# mcore-h616-breakout-RevA1.net
KiCad netlist of a schematic drawn in EAGLE
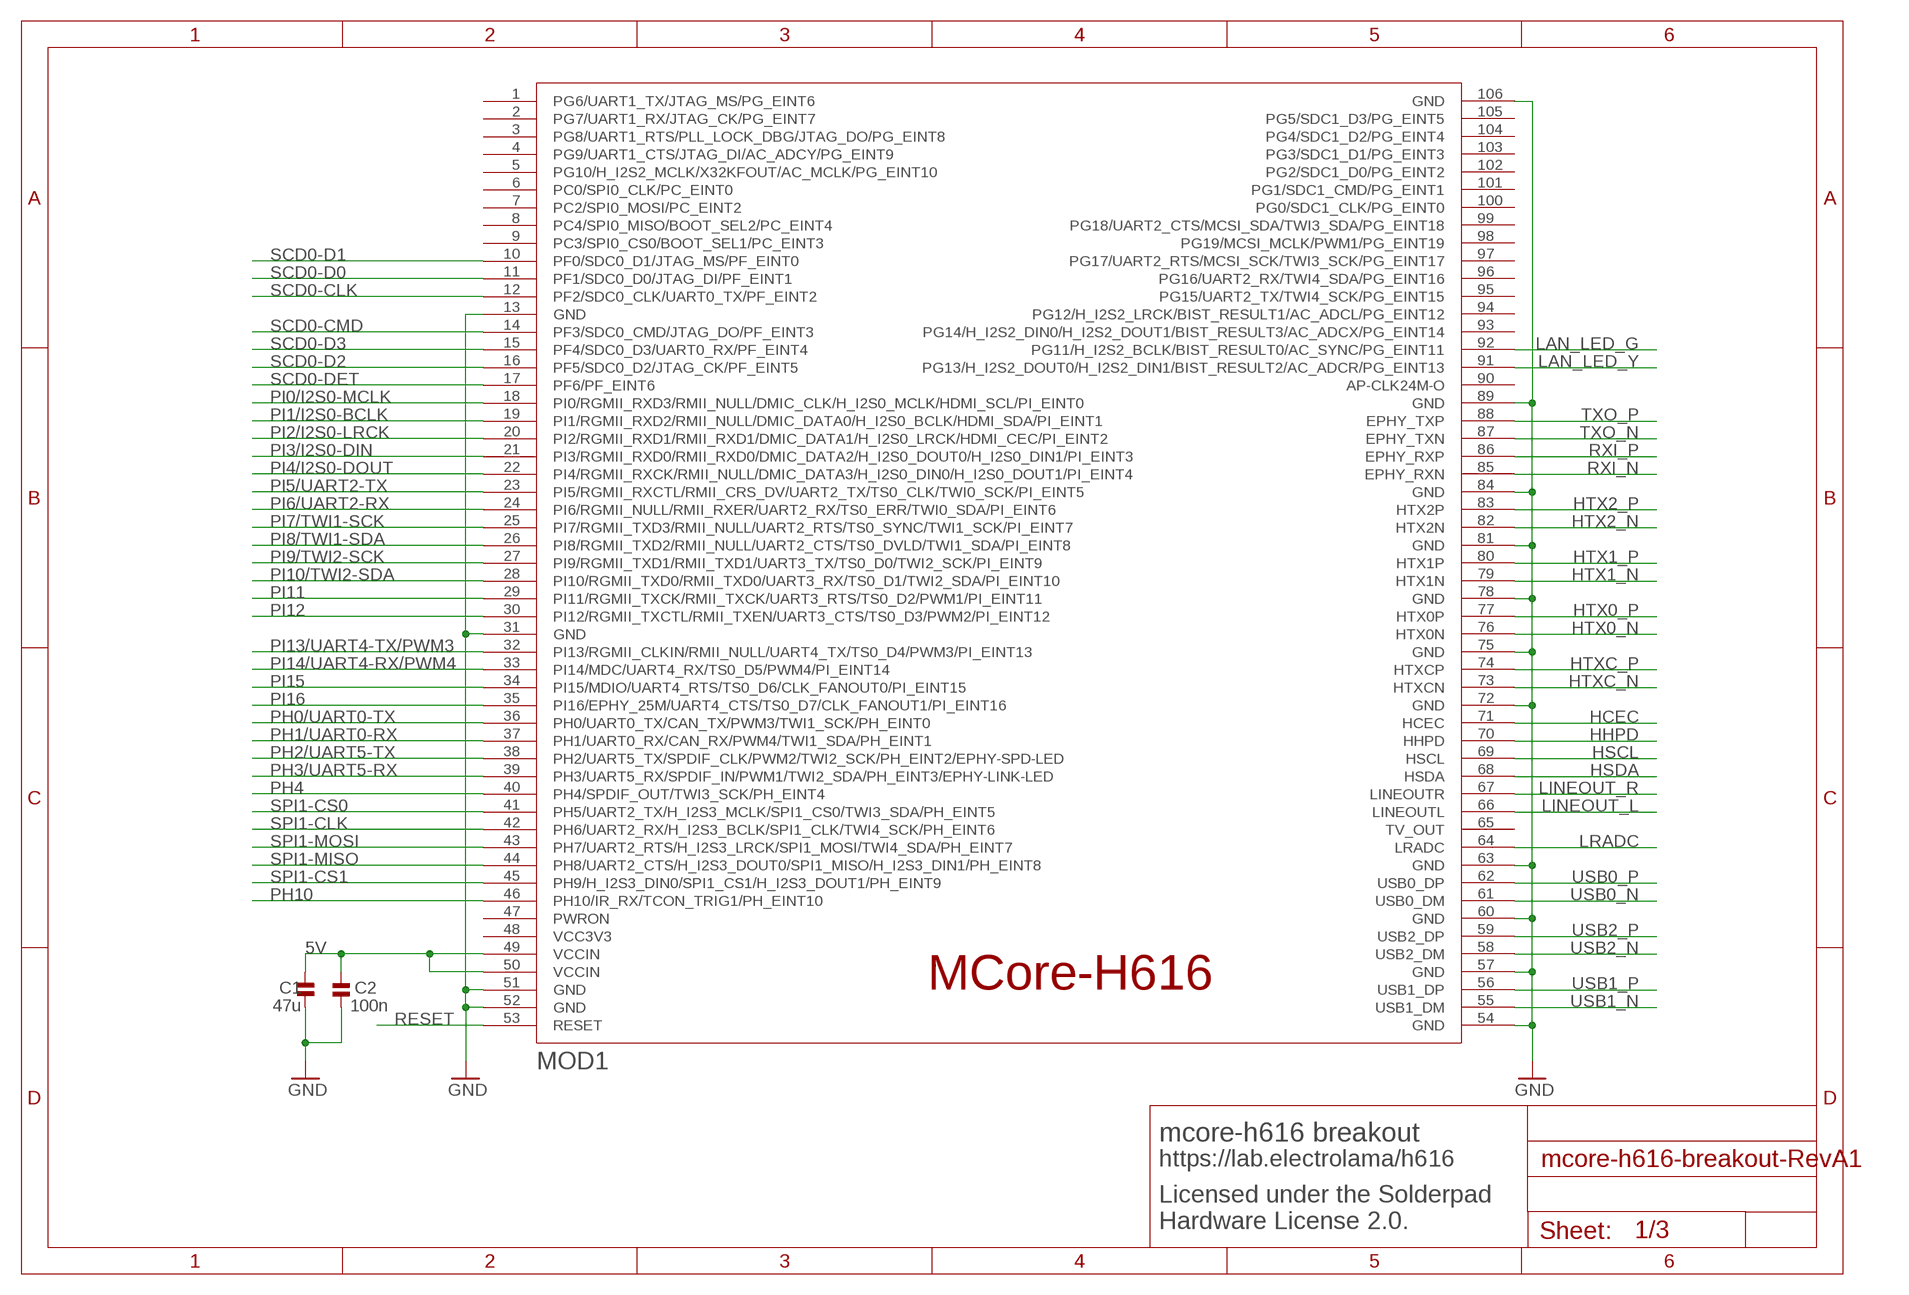
[diagram p0: schematic, sheet 1]
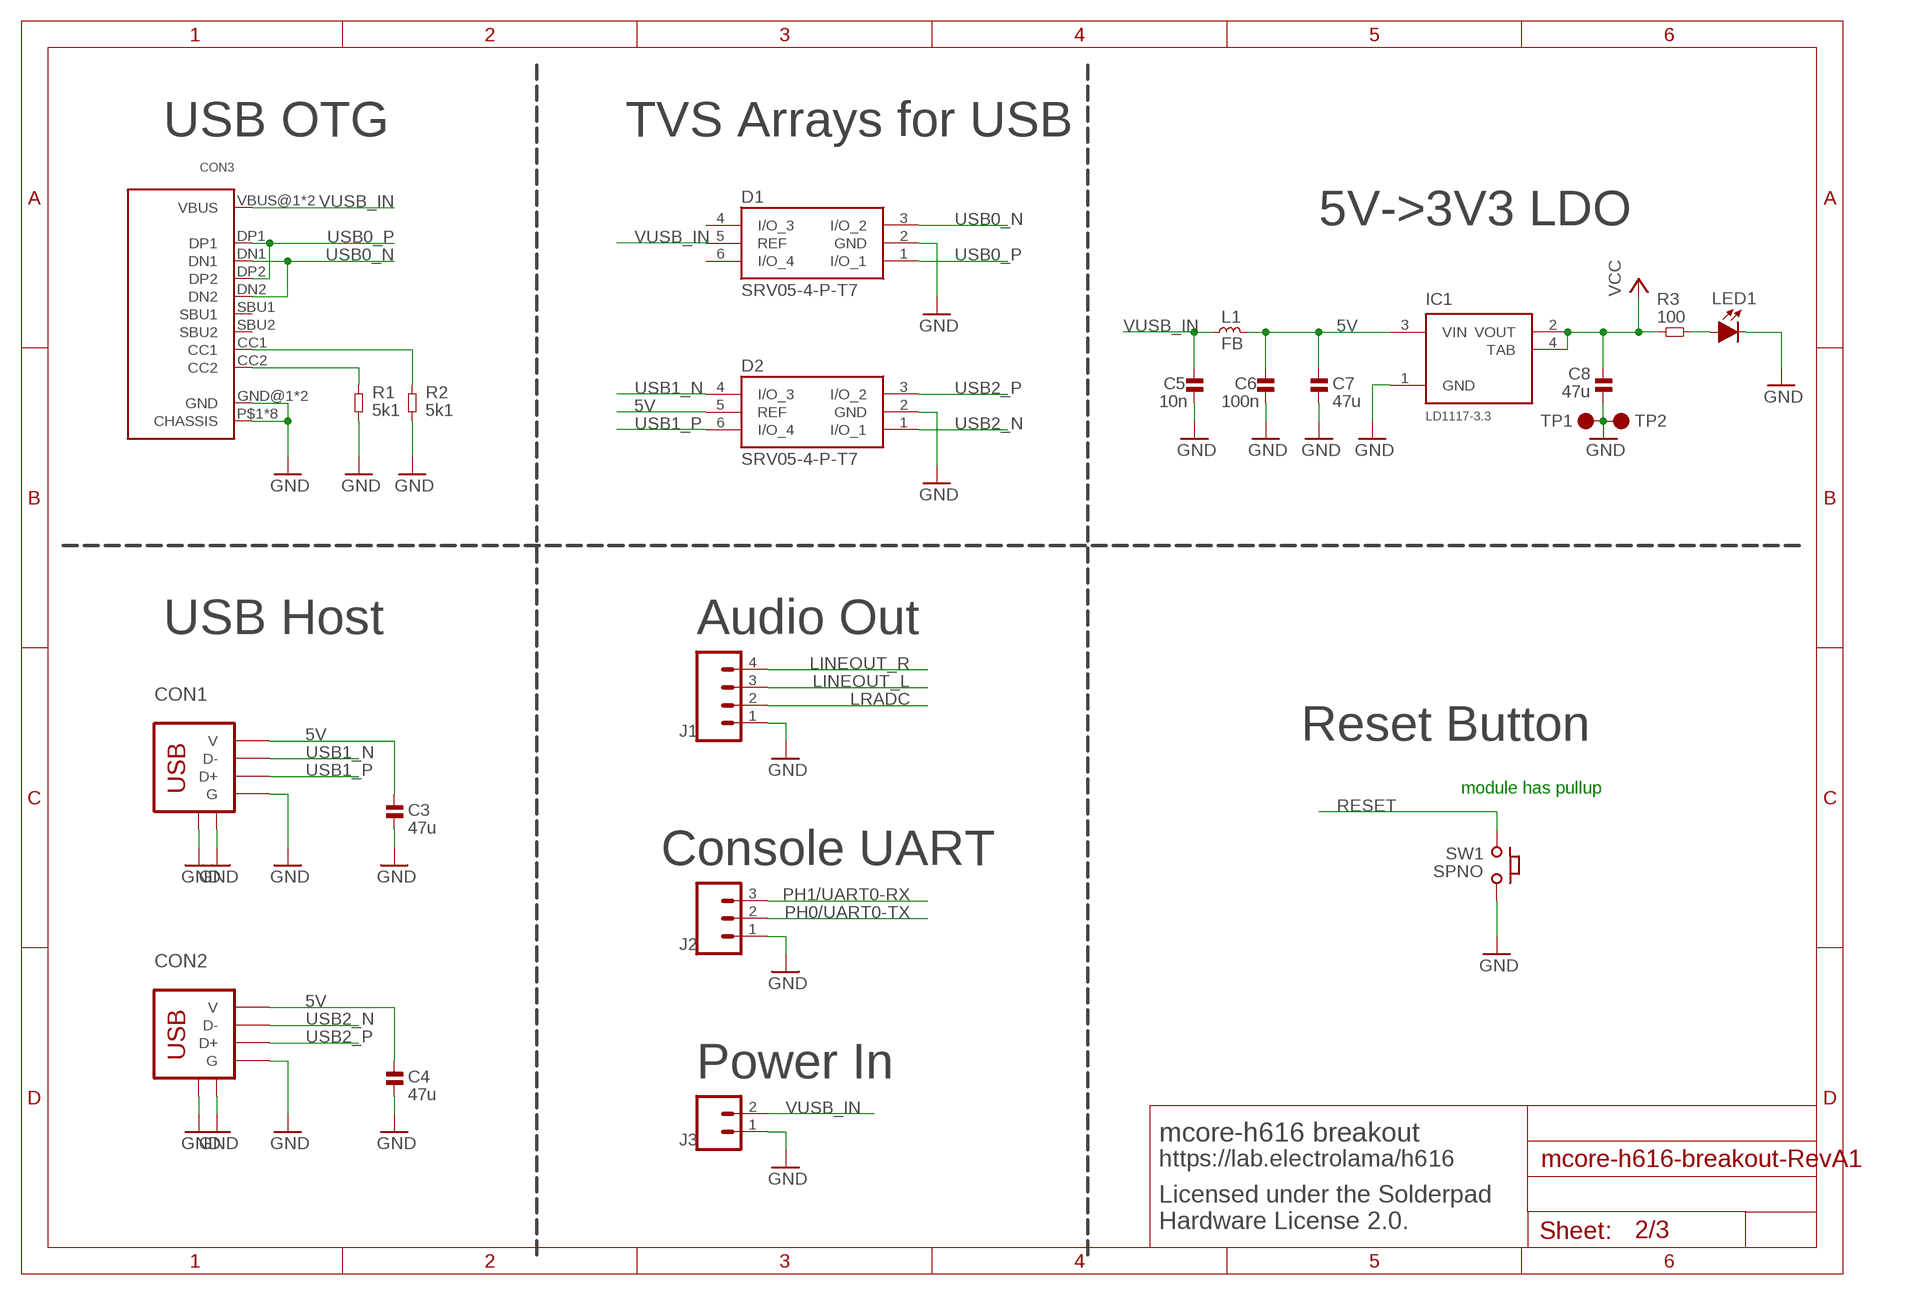
[diagram p1: schematic, sheet 2]
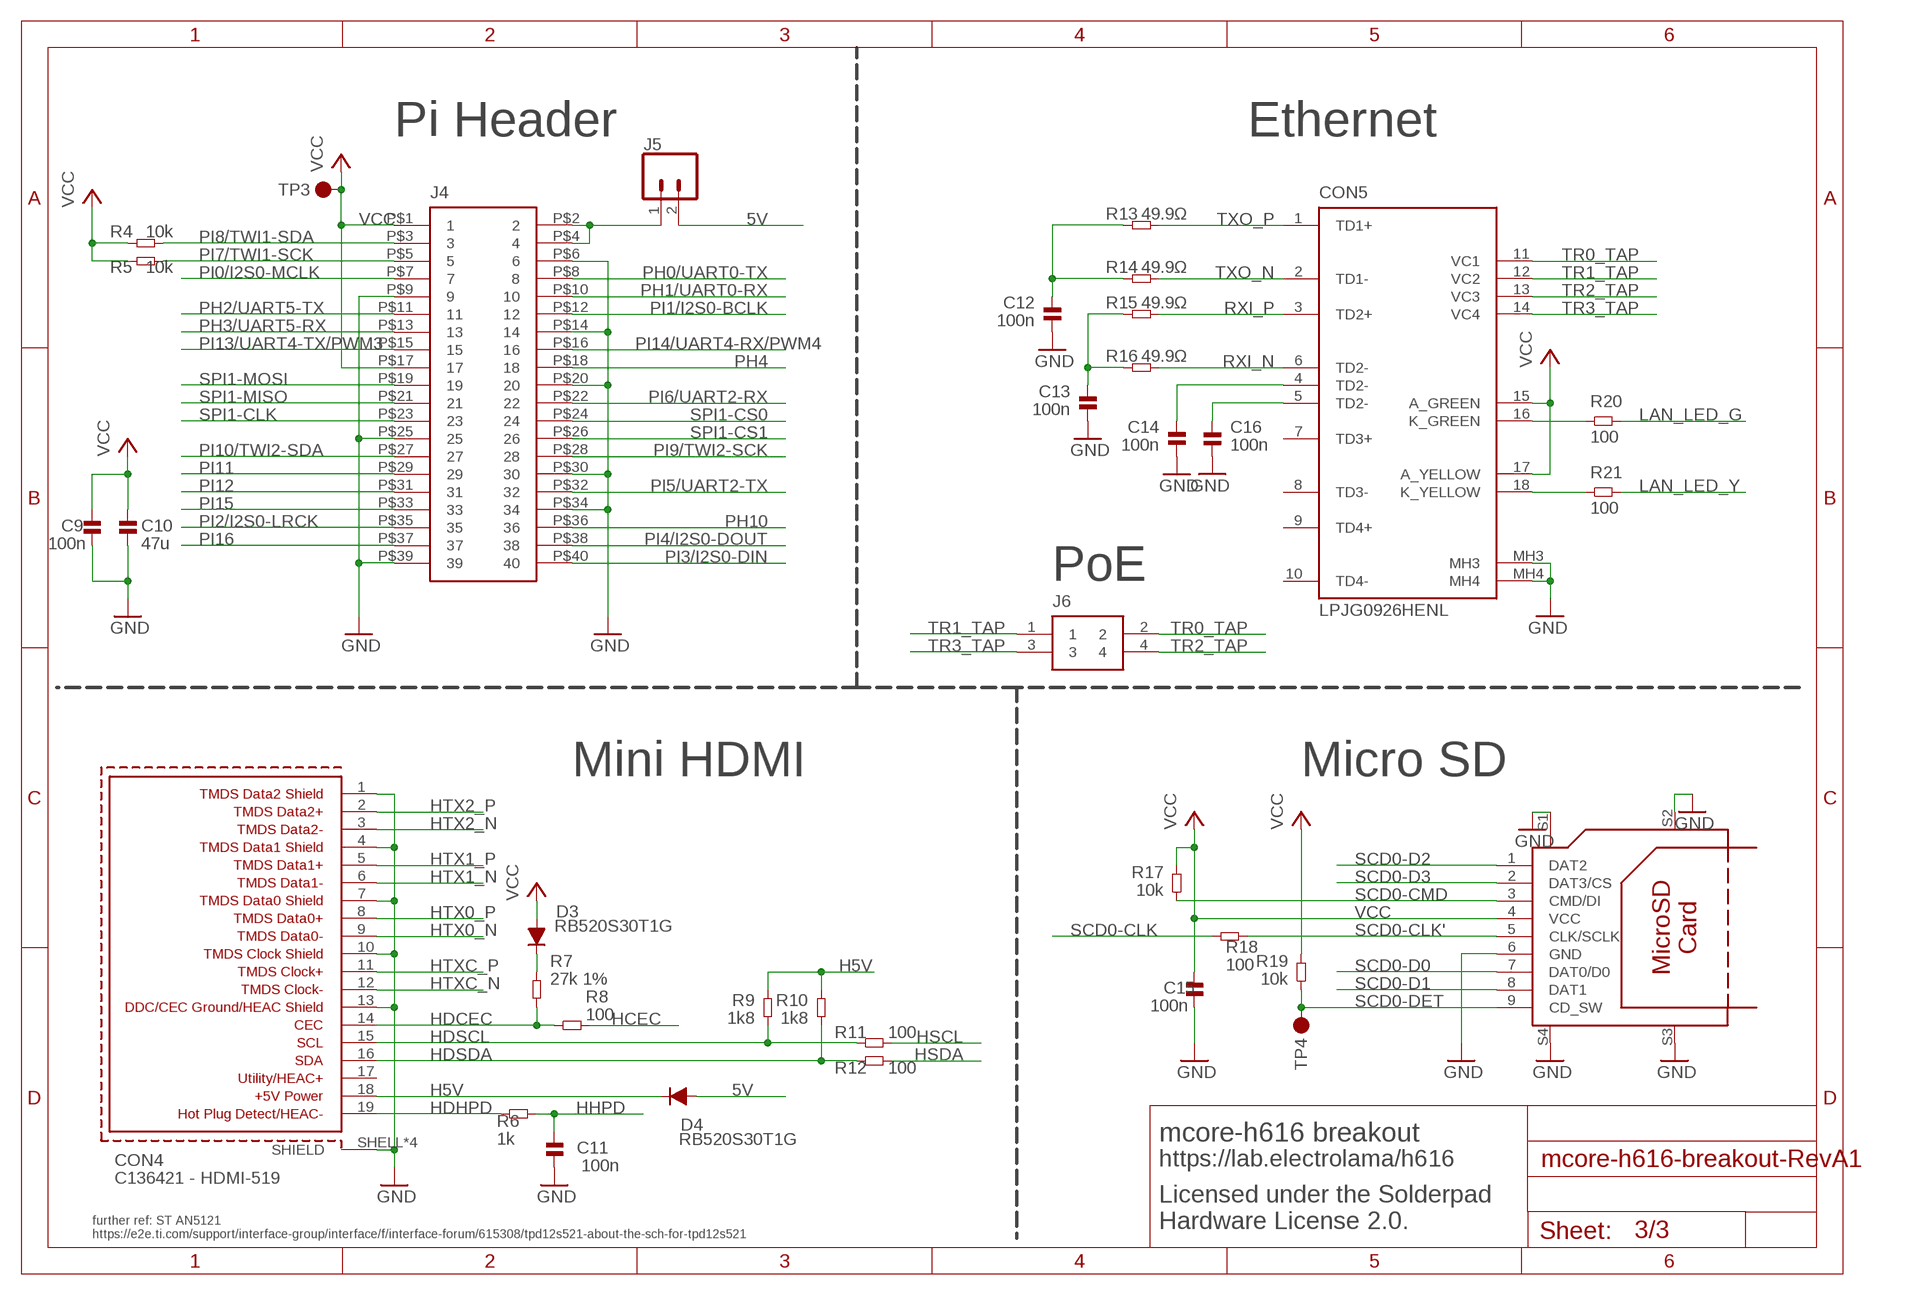
[diagram p2: schematic, sheet 3]

(export (version "E")
  (design (tool "Eeschema 10.0.6"))
  (components
    (comp (ref "C3")
      (value "47u")
      (footprint "eagle-import:_PKG_C_1206")
      (libsource (lib "eagle-import") (part "CAP-1206"))
    )
    (comp (ref "C4")
      (value "47u")
      (footprint "eagle-import:_PKG_C_1206")
      (libsource (lib "eagle-import") (part "CAP-1206"))
    )
    (comp (ref "C5")
      (value "10n")
      (footprint "eagle-import:_PKG_C_0402")
      (libsource (lib "eagle-import") (part "CAP-0402"))
    )
    (comp (ref "C6")
      (value "100n")
      (footprint "eagle-import:_PKG_C_0402")
      (libsource (lib "eagle-import") (part "CAP-0402"))
    )
    (comp (ref "C7")
      (value "47u")
      (footprint "eagle-import:_PKG_C_1206")
      (libsource (lib "eagle-import") (part "CAP-1206"))
    )
    (comp (ref "C8")
      (value "47u")
      (footprint "eagle-import:_PKG_C_1206")
      (libsource (lib "eagle-import") (part "CAP-1206"))
    )
    (comp (ref "CON1")
      (value "USB-A-FEMALE-JING-912-121A2023S10100")
      (footprint "eagle-import:JING_912-121A2023S10100")
      (libsource (lib "eagle-import") (part "USB-A-FEMALE-JING-912-121A2023S10100"))
    )
    (comp (ref "CON2")
      (value "USB-A-FEMALE-JING-912-121A2023S10100")
      (footprint "eagle-import:JING_912-121A2023S10100")
      (libsource (lib "eagle-import") (part "USB-A-FEMALE-JING-912-121A2023S10100"))
    )
    (comp (ref "CON3")
      (value "USBC_USB-C-12")
      (footprint "eagle-import:USBC_C-31-M-12")
      (libsource (lib "eagle-import") (part "USBC_USB-C-12"))
    )
    (comp (ref "D1")
      (value "SRV05-4-P-T7")
      (footprint "eagle-import:SOT95P280X145-6N")
      (libsource (lib "eagle-import") (part "DIODE-TVS-SRV05-4"))
    )
    (comp (ref "D2")
      (value "SRV05-4-P-T7")
      (footprint "eagle-import:SOT95P280X145-6N")
      (libsource (lib "eagle-import") (part "DIODE-TVS-SRV05-4"))
    )
    (comp (ref "IC1")
      (value "LD1117-3.3")
      (footprint "eagle-import:_PKG_SOT223-4_TI-DCY4")
      (libsource (lib "eagle-import") (part "POWER-LDO-LD1117-SOT223-4"))
    )
    (comp (ref "J1")
      (value "CONN_04LOCK")
      (footprint "eagle-import:1X04_LOCK")
      (libsource (lib "eagle-import") (part "CONN_04LOCK"))
    )
    (comp (ref "J2")
      (value "CONN_03LOCK")
      (footprint "eagle-import:1X03_LOCK")
      (libsource (lib "eagle-import") (part "CONN_03LOCK"))
    )
    (comp (ref "J3")
      (value "CONN_02LOCK")
      (footprint "eagle-import:1X02_LOCK")
      (libsource (lib "eagle-import") (part "CONN_02LOCK"))
    )
    (comp (ref "L1")
      (value "FB")
      (footprint "eagle-import:_PKG_C_0805")
      (libsource (lib "eagle-import") (part "INDUCTOR-0805"))
    )
    (comp (ref "LED1")
      (value "LED-0805")
      (footprint "eagle-import:_PKG_LED_0805")
      (libsource (lib "eagle-import") (part "LED-0805"))
    )
    (comp (ref "R1")
      (value "5k1")
      (footprint "eagle-import:_PKG_R_0402")
      (libsource (lib "eagle-import") (part "RES-0402"))
    )
    (comp (ref "R2")
      (value "5k1")
      (footprint "eagle-import:_PKG_R_0402")
      (libsource (lib "eagle-import") (part "RES-0402"))
    )
    (comp (ref "R3")
      (value "100")
      (footprint "eagle-import:_PKG_R_0402")
      (libsource (lib "eagle-import") (part "RES-0402"))
    )
    (comp (ref "SW1")
      (value "SPNO")
      (footprint "eagle-import:GENERIC_SPNO_4P_6X6MM")
      (libsource (lib "eagle-import") (part "PUSHBUTTON-6X6MM"))
    )
    (comp (ref "TP1")
      (value "TP")
      (footprint "eagle-import:TP_DOT_1.5X1.5MM")
      (libsource (lib "eagle-import") (part "TP"))
    )
    (comp (ref "TP2")
      (value "TP")
      (footprint "eagle-import:TP_DOT_1.5X1.5MM")
      (libsource (lib "eagle-import") (part "TP"))
    )
    (comp (ref "C9")
      (value "100n")
      (footprint "eagle-import:_PKG_C_0402")
      (libsource (lib "eagle-import") (part "CAP-0402"))
    )
    (comp (ref "C10")
      (value "47u")
      (footprint "eagle-import:_PKG_C_1206")
      (libsource (lib "eagle-import") (part "CAP-1206"))
    )
    (comp (ref "C11")
      (value "100n")
      (footprint "eagle-import:_PKG_C_0402")
      (libsource (lib "eagle-import") (part "CAP-0402"))
    )
    (comp (ref "C12")
      (value "100n")
      (footprint "eagle-import:_PKG_C_0402")
      (libsource (lib "eagle-import") (part "CAP-0402"))
    )
    (comp (ref "C13")
      (value "100n")
      (footprint "eagle-import:_PKG_C_0402")
      (libsource (lib "eagle-import") (part "CAP-0402"))
    )
    (comp (ref "C14")
      (value "100n")
      (footprint "eagle-import:_PKG_C_0402")
      (libsource (lib "eagle-import") (part "CAP-0402"))
    )
    (comp (ref "C15")
      (value "100n")
      (footprint "eagle-import:_PKG_C_0402")
      (libsource (lib "eagle-import") (part "CAP-0402"))
    )
    (comp (ref "C16")
      (value "100n")
      (footprint "eagle-import:_PKG_C_0402")
      (libsource (lib "eagle-import") (part "CAP-0402"))
    )
    (comp (ref "CON4")
      (value "C136421 - HDMI-519")
      (footprint "eagle-import:685119136923")
      (libsource (lib "eagle-import") (part "685119136923"))
    )
    (comp (ref "CON5")
      (value "LPJG0926HENL")
      (footprint "eagle-import:LPJG0926HENL")
      (libsource (lib "eagle-import") (part "RJ45_POE_LPJG0926HENL"))
    )
    (comp (ref "CON6")
      (value "C111196 - TF-15x15")
      (footprint "eagle-import:TF_SHENZHEN-SPECIAL")
      (libsource (lib "eagle-import") (part "TF/SHENZHEN-SPECIAL"))
    )
    (comp (ref "D3")
      (value "RB520S30T1G")
      (footprint "eagle-import:_PKG_SOD523")
      (libsource (lib "eagle-import") (part "DIODE-SCHOTTKY-RB520S30"))
    )
    (comp (ref "D4")
      (value "RB520S30T1G")
      (footprint "eagle-import:_PKG_SOD523")
      (libsource (lib "eagle-import") (part "DIODE-SCHOTTKY-RB520S30"))
    )
    (comp (ref "J4")
      (value "CON_2.54MM_TH_2X20")
      (footprint "eagle-import:CON_2.54MM_TH_2X20")
      (libsource (lib "eagle-import") (part "CON_2.54MM_TH_2X20"))
    )
    (comp (ref "J5")
      (value "CONN_02LOCK")
      (footprint "eagle-import:1X02_LOCK")
      (libsource (lib "eagle-import") (part "CONN_02LOCK"))
    )
    (comp (ref "J6")
      (value "CON_2.54MM_TH_2X2")
      (footprint "eagle-import:CON_2.54MM_TH_2X2")
      (libsource (lib "eagle-import") (part "CON_2.54MM_TH_2X2"))
    )
    (comp (ref "R4")
      (value "10k")
      (footprint "eagle-import:_PKG_R_0402")
      (libsource (lib "eagle-import") (part "RES-0402"))
    )
    (comp (ref "R5")
      (value "10k")
      (footprint "eagle-import:_PKG_R_0402")
      (libsource (lib "eagle-import") (part "RES-0402"))
    )
    (comp (ref "R6")
      (value "1k")
      (footprint "eagle-import:_PKG_R_0402")
      (libsource (lib "eagle-import") (part "RES-0402"))
    )
    (comp (ref "R7")
      (value "27k 1%")
      (footprint "eagle-import:_PKG_R_0402")
      (libsource (lib "eagle-import") (part "RES-0402"))
    )
    (comp (ref "R8")
      (value "100")
      (footprint "eagle-import:_PKG_R_0402")
      (libsource (lib "eagle-import") (part "RES-0402"))
    )
    (comp (ref "R9")
      (value "1k8")
      (footprint "eagle-import:_PKG_R_0402")
      (libsource (lib "eagle-import") (part "RES-0402"))
    )
    (comp (ref "R10")
      (value "1k8")
      (footprint "eagle-import:_PKG_R_0402")
      (libsource (lib "eagle-import") (part "RES-0402"))
    )
    (comp (ref "R11")
      (value "100")
      (footprint "eagle-import:_PKG_R_0402")
      (libsource (lib "eagle-import") (part "RES-0402"))
    )
    (comp (ref "R12")
      (value "100")
      (footprint "eagle-import:_PKG_R_0402")
      (libsource (lib "eagle-import") (part "RES-0402"))
    )
    (comp (ref "R13")
      (value "49.9Ω")
      (footprint "eagle-import:_PKG_R_0402")
      (libsource (lib "eagle-import") (part "RES-0402"))
    )
    (comp (ref "R14")
      (value "49.9Ω")
      (footprint "eagle-import:_PKG_R_0402")
      (libsource (lib "eagle-import") (part "RES-0402"))
    )
    (comp (ref "R15")
      (value "49.9Ω")
      (footprint "eagle-import:_PKG_R_0402")
      (libsource (lib "eagle-import") (part "RES-0402"))
    )
    (comp (ref "R16")
      (value "49.9Ω")
      (footprint "eagle-import:_PKG_R_0402")
      (libsource (lib "eagle-import") (part "RES-0402"))
    )
    (comp (ref "R17")
      (value "10k")
      (footprint "eagle-import:_PKG_R_0402")
      (libsource (lib "eagle-import") (part "RES-0402"))
    )
    (comp (ref "R18")
      (value "100")
      (footprint "eagle-import:_PKG_R_0402")
      (libsource (lib "eagle-import") (part "RES-0402"))
    )
    (comp (ref "R19")
      (value "10k")
      (footprint "eagle-import:_PKG_R_0402")
      (libsource (lib "eagle-import") (part "RES-0402"))
    )
    (comp (ref "R20")
      (value "100")
      (footprint "eagle-import:_PKG_R_0402")
      (libsource (lib "eagle-import") (part "RES-0402"))
    )
    (comp (ref "R21")
      (value "100")
      (footprint "eagle-import:_PKG_R_0402")
      (libsource (lib "eagle-import") (part "RES-0402"))
    )
    (comp (ref "TP3")
      (value "TP")
      (footprint "eagle-import:TP_DOT_1.5X1.5MM")
      (libsource (lib "eagle-import") (part "TP"))
    )
    (comp (ref "TP4")
      (value "TP")
      (footprint "eagle-import:TP_DOT_1.5X1.5MM")
      (libsource (lib "eagle-import") (part "TP"))
    )
    (comp (ref "C1")
      (value "47u")
      (footprint "eagle-import:_PKG_C_1206")
      (libsource (lib "eagle-import") (part "CAP-1206"))
    )
    (comp (ref "C2")
      (value "100n")
      (footprint "eagle-import:_PKG_C_0402")
      (libsource (lib "eagle-import") (part "CAP-0402"))
    )
    (comp (ref "MOD1")
      (value "WIDORA_MCORE-H616_V1")
      (footprint "eagle-import:MCORE-H616_V1")
      (libsource (lib "eagle-import") (part "WIDORA_MCORE-H616_V1"))
    )
  )
  (nets
    (net (code "1") (name "5V") (class "Default")
      (node (ref "C1") (pin "2") (pinfunction "2_2") (pintype "passive"))
      (node (ref "C2") (pin "2") (pinfunction "2_2") (pintype "passive"))
      (node (ref "C3") (pin "2") (pinfunction "2_2") (pintype "passive"))
      (node (ref "C4") (pin "2") (pinfunction "2_2") (pintype "passive"))
      (node (ref "C6") (pin "2") (pinfunction "2_2") (pintype "passive"))
      (node (ref "C7") (pin "2") (pinfunction "2_2") (pintype "passive"))
      (node (ref "CON1") (pin "VBUS") (pinfunction "V_VBUS") (pintype "bidirectional"))
      (node (ref "CON2") (pin "VBUS") (pinfunction "V_VBUS") (pintype "bidirectional"))
      (node (ref "D2") (pin "5") (pinfunction "REF_5") (pintype "bidirectional"))
      (node (ref "D4") (pin "2") (pinfunction "A_2") (pintype "passive"))
      (node (ref "IC1") (pin "3") (pinfunction "VIN_3") (pintype "output"))
      (node (ref "J5") (pin "2") (pinfunction "2_2") (pintype "passive"))
      (node (ref "L1") (pin "2") (pinfunction "2_2") (pintype "passive"))
      (node (ref "MOD1") (pin "49") (pinfunction "VCCIN_49") (pintype "input"))
      (node (ref "MOD1") (pin "50") (pinfunction "VCCIN_50") (pintype "input"))
    )
    (net (code "2") (name "GND") (class "Default")
      (node (ref "C1") (pin "1") (pinfunction "1_1") (pintype "passive"))
      (node (ref "C10") (pin "1") (pinfunction "1_1") (pintype "passive"))
      (node (ref "C11") (pin "1") (pinfunction "1_1") (pintype "passive"))
      (node (ref "C12") (pin "1") (pinfunction "1_1") (pintype "passive"))
      (node (ref "C13") (pin "1") (pinfunction "1_1") (pintype "passive"))
      (node (ref "C14") (pin "1") (pinfunction "1_1") (pintype "passive"))
      (node (ref "C15") (pin "1") (pinfunction "1_1") (pintype "passive"))
      (node (ref "C16") (pin "1") (pinfunction "1_1") (pintype "passive"))
      (node (ref "C2") (pin "1") (pinfunction "1_1") (pintype "passive"))
      (node (ref "C3") (pin "1") (pinfunction "1_1") (pintype "passive"))
      (node (ref "C4") (pin "1") (pinfunction "1_1") (pintype "passive"))
      (node (ref "C5") (pin "1") (pinfunction "1_1") (pintype "passive"))
      (node (ref "C6") (pin "1") (pinfunction "1_1") (pintype "passive"))
      (node (ref "C7") (pin "1") (pinfunction "1_1") (pintype "passive"))
      (node (ref "C8") (pin "1") (pinfunction "1_1") (pintype "passive"))
      (node (ref "C9") (pin "1") (pinfunction "1_1") (pintype "passive"))
      (node (ref "CON1") (pin "GND") (pinfunction "G_GND") (pintype "bidirectional"))
      (node (ref "CON1") (pin "P$5") (pinfunction "SHIELD1_P$5") (pintype "bidirectional"))
      (node (ref "CON1") (pin "P$6") (pinfunction "SHIELD2_P$6") (pintype "bidirectional"))
      (node (ref "CON2") (pin "GND") (pinfunction "G_GND") (pintype "bidirectional"))
      (node (ref "CON2") (pin "P$5") (pinfunction "SHIELD1_P$5") (pintype "bidirectional"))
      (node (ref "CON2") (pin "P$6") (pinfunction "SHIELD2_P$6") (pintype "bidirectional"))
      (node (ref "CON3") (pin "GND@1") (pinfunction "GND_GND@1") (pintype "bidirectional"))
      (node (ref "CON3") (pin "GND@2") (pinfunction "GND_GND@2") (pintype "bidirectional"))
      (node (ref "CON3") (pin "P$1") (pinfunction "CHASSIS_P$1") (pintype "bidirectional"))
      (node (ref "CON3") (pin "P$2") (pinfunction "CHASSIS_P$2") (pintype "bidirectional"))
      (node (ref "CON3") (pin "P$3") (pinfunction "CHASSIS_P$3") (pintype "bidirectional"))
      (node (ref "CON3") (pin "P$4") (pinfunction "CHASSIS_P$4") (pintype "bidirectional"))
      (node (ref "CON3") (pin "P$5") (pinfunction "CHASSIS_P$5") (pintype "bidirectional"))
      (node (ref "CON3") (pin "P$6") (pinfunction "CHASSIS_P$6") (pintype "bidirectional"))
      (node (ref "CON3") (pin "P$7") (pinfunction "CHASSIS_P$7") (pintype "bidirectional"))
      (node (ref "CON3") (pin "P$8") (pinfunction "CHASSIS_P$8") (pintype "bidirectional"))
      (node (ref "CON4") (pin "1") (pinfunction "TMDSDATA2SHIELD_1") (pintype "passive"))
      (node (ref "CON4") (pin "10") (pinfunction "TMDSCLOCKSHIELD_10") (pintype "passive"))
      (node (ref "CON4") (pin "13") (pinfunction "DDC/CECGROUND/HEACSHIELD_13") (pintype "passive"))
      (node (ref "CON4") (pin "4") (pinfunction "TMDSDATA1SHIELD_4") (pintype "passive"))
      (node (ref "CON4") (pin "7") (pinfunction "TMDSDATA0SHIELD_7") (pintype "passive"))
      (node (ref "CON4") (pin "SHELL") (pinfunction "SHIELD_SHELL") (pintype "passive"))
      (node (ref "CON4") (pin "SHELL1") (pinfunction "SHIELD_SHELL1") (pintype "passive"))
      (node (ref "CON4") (pin "SHELL2") (pinfunction "SHIELD_SHELL2") (pintype "passive"))
      (node (ref "CON4") (pin "SHELL3") (pinfunction "SHIELD_SHELL3") (pintype "passive"))
      (node (ref "CON5") (pin "MH3") (pinfunction "MH3_MH3") (pintype "bidirectional"))
      (node (ref "CON5") (pin "MH4") (pinfunction "MH4_MH4") (pintype "bidirectional"))
      (node (ref "CON6") (pin "6") (pinfunction "GND_6") (pintype "bidirectional"))
      (node (ref "CON6") (pin "S1") (pinfunction "S1_S1") (pintype "bidirectional"))
      (node (ref "CON6") (pin "S2") (pinfunction "S2_S2") (pintype "bidirectional"))
      (node (ref "CON6") (pin "S3") (pinfunction "S3_S3") (pintype "bidirectional"))
      (node (ref "CON6") (pin "S4") (pinfunction "S4_S4") (pintype "bidirectional"))
      (node (ref "D1") (pin "2") (pinfunction "GND_2") (pintype "bidirectional"))
      (node (ref "D2") (pin "2") (pinfunction "GND_2") (pintype "bidirectional"))
      (node (ref "IC1") (pin "1") (pinfunction "GND_1") (pintype "output"))
      (node (ref "J1") (pin "1") (pinfunction "1_1") (pintype "passive"))
      (node (ref "J2") (pin "1") (pinfunction "1_1") (pintype "passive"))
      (node (ref "J3") (pin "1") (pinfunction "1_1") (pintype "passive"))
      (node (ref "J4") (pin "P$14") (pinfunction "14_P$14") (pintype "bidirectional"))
      (node (ref "J4") (pin "P$20") (pinfunction "20_P$20") (pintype "bidirectional"))
      (node (ref "J4") (pin "P$25") (pinfunction "25_P$25") (pintype "bidirectional"))
      (node (ref "J4") (pin "P$30") (pinfunction "30_P$30") (pintype "bidirectional"))
      (node (ref "J4") (pin "P$34") (pinfunction "34_P$34") (pintype "bidirectional"))
      (node (ref "J4") (pin "P$39") (pinfunction "39_P$39") (pintype "bidirectional"))
      (node (ref "J4") (pin "P$6") (pinfunction "6_P$6") (pintype "bidirectional"))
      (node (ref "J4") (pin "P$9") (pinfunction "9_P$9") (pintype "bidirectional"))
      (node (ref "LED1") (pin "C") (pinfunction "C_C") (pintype "passive"))
      (node (ref "MOD1") (pin "106") (pinfunction "GND_106") (pintype "passive"))
      (node (ref "MOD1") (pin "13") (pinfunction "GND_13") (pintype "passive"))
      (node (ref "MOD1") (pin "31") (pinfunction "GND_31") (pintype "passive"))
      (node (ref "MOD1") (pin "51") (pinfunction "GND_51") (pintype "passive"))
      (node (ref "MOD1") (pin "52") (pinfunction "GND_52") (pintype "passive"))
      (node (ref "MOD1") (pin "54") (pinfunction "GND_54") (pintype "passive"))
      (node (ref "MOD1") (pin "57") (pinfunction "GND_57") (pintype "passive"))
      (node (ref "MOD1") (pin "60") (pinfunction "GND_60") (pintype "passive"))
      (node (ref "MOD1") (pin "63") (pinfunction "GND_63") (pintype "passive"))
      (node (ref "MOD1") (pin "72") (pinfunction "GND_72") (pintype "passive"))
      (node (ref "MOD1") (pin "75") (pinfunction "GND_75") (pintype "passive"))
      (node (ref "MOD1") (pin "78") (pinfunction "GND_78") (pintype "passive"))
      (node (ref "MOD1") (pin "81") (pinfunction "GND_81") (pintype "passive"))
      (node (ref "MOD1") (pin "84") (pinfunction "GND_84") (pintype "passive"))
      (node (ref "MOD1") (pin "89") (pinfunction "GND_89") (pintype "passive"))
      (node (ref "R1") (pin "1") (pinfunction "1_1") (pintype "passive"))
      (node (ref "R2") (pin "1") (pinfunction "1_1") (pintype "passive"))
      (node (ref "SW1") (pin "P$3") (pinfunction "2_P$3") (pintype "bidirectional"))
      (node (ref "SW1") (pin "P$4") (pinfunction "2_P$4") (pintype "bidirectional"))
      (node (ref "TP1") (pin "TP") (pinfunction "TP_TP") (pintype "bidirectional"))
      (node (ref "TP2") (pin "TP") (pinfunction "TP_TP") (pintype "bidirectional"))
    )
    (net (code "3") (name "H5V") (class "Default")
      (node (ref "CON4") (pin "18") (pinfunction "+5VPOWER_18") (pintype "power_in"))
      (node (ref "D4") (pin "1") (pinfunction "C_1") (pintype "passive"))
      (node (ref "R10") (pin "1") (pinfunction "1_1") (pintype "passive"))
      (node (ref "R9") (pin "1") (pinfunction "1_1") (pintype "passive"))
    )
    (net (code "4") (name "HCEC") (class "Default")
      (node (ref "MOD1") (pin "71") (pinfunction "HCEC_71") (pintype "passive"))
      (node (ref "R8") (pin "2") (pinfunction "2_2") (pintype "passive"))
    )
    (net (code "5") (name "HDCEC") (class "Default")
      (node (ref "CON4") (pin "14") (pinfunction "CEC_14") (pintype "passive"))
      (node (ref "R7") (pin "1") (pinfunction "1_1") (pintype "passive"))
      (node (ref "R8") (pin "1") (pinfunction "1_1") (pintype "passive"))
    )
    (net (code "6") (name "HDHPD") (class "Default")
      (node (ref "CON4") (pin "19") (pinfunction "HOTPLUGDETECT/HEAC-_19") (pintype "passive"))
      (node (ref "R6") (pin "1") (pinfunction "1_1") (pintype "passive"))
    )
    (net (code "7") (name "HDSCL") (class "Default")
      (node (ref "CON4") (pin "15") (pinfunction "SCL_15") (pintype "passive"))
      (node (ref "R11") (pin "1") (pinfunction "1_1") (pintype "passive"))
      (node (ref "R9") (pin "2") (pinfunction "2_2") (pintype "passive"))
    )
    (net (code "8") (name "HDSDA") (class "Default")
      (node (ref "CON4") (pin "16") (pinfunction "SDA_16") (pintype "passive"))
      (node (ref "R10") (pin "2") (pinfunction "2_2") (pintype "passive"))
      (node (ref "R12") (pin "1") (pinfunction "1_1") (pintype "passive"))
    )
    (net (code "9") (name "HHPD") (class "Default")
      (node (ref "C11") (pin "2") (pinfunction "2_2") (pintype "passive"))
      (node (ref "MOD1") (pin "70") (pinfunction "HHPD_70") (pintype "passive"))
      (node (ref "R6") (pin "2") (pinfunction "2_2") (pintype "passive"))
    )
    (net (code "10") (name "HSCL") (class "Default")
      (node (ref "MOD1") (pin "69") (pinfunction "HSCL_69") (pintype "passive"))
      (node (ref "R11") (pin "2") (pinfunction "2_2") (pintype "passive"))
    )
    (net (code "11") (name "HSDA") (class "Default")
      (node (ref "MOD1") (pin "68") (pinfunction "HSDA_68") (pintype "passive"))
      (node (ref "R12") (pin "2") (pinfunction "2_2") (pintype "passive"))
    )
    (net (code "12") (name "HTX0_N") (class "Default")
      (node (ref "CON4") (pin "9") (pinfunction "TMDSDATA0-_9") (pintype "passive"))
      (node (ref "MOD1") (pin "76") (pinfunction "HTX0N_76") (pintype "passive"))
    )
    (net (code "13") (name "HTX0_P") (class "Default")
      (node (ref "CON4") (pin "8") (pinfunction "TMDSDATA0+_8") (pintype "passive"))
      (node (ref "MOD1") (pin "77") (pinfunction "HTX0P_77") (pintype "passive"))
    )
    (net (code "14") (name "HTX1_N") (class "Default")
      (node (ref "CON4") (pin "6") (pinfunction "TMDSDATA1-_6") (pintype "passive"))
      (node (ref "MOD1") (pin "79") (pinfunction "HTX1N_79") (pintype "passive"))
    )
    (net (code "15") (name "HTX1_P") (class "Default")
      (node (ref "CON4") (pin "5") (pinfunction "TMDSDATA1+_5") (pintype "passive"))
      (node (ref "MOD1") (pin "80") (pinfunction "HTX1P_80") (pintype "passive"))
    )
    (net (code "16") (name "HTX2_N") (class "Default")
      (node (ref "CON4") (pin "3") (pinfunction "TMDSDATA2-_3") (pintype "passive"))
      (node (ref "MOD1") (pin "82") (pinfunction "HTX2N_82") (pintype "passive"))
    )
    (net (code "17") (name "HTX2_P") (class "Default")
      (node (ref "CON4") (pin "2") (pinfunction "TMDSDATA2+_2") (pintype "passive"))
      (node (ref "MOD1") (pin "83") (pinfunction "HTX2P_83") (pintype "passive"))
    )
    (net (code "18") (name "HTXC_N") (class "Default")
      (node (ref "CON4") (pin "12") (pinfunction "TMDSCLOCK-_12") (pintype "passive"))
      (node (ref "MOD1") (pin "73") (pinfunction "HTXCN_73") (pintype "passive"))
    )
    (net (code "19") (name "HTXC_P") (class "Default")
      (node (ref "CON4") (pin "11") (pinfunction "TMDSCLOCK+_11") (pintype "passive"))
      (node (ref "MOD1") (pin "74") (pinfunction "HTXCP_74") (pintype "passive"))
    )
    (net (code "20") (name "LAN_LED_G") (class "Default")
      (node (ref "MOD1") (pin "92") (pinfunction "PG11/H_I2S2_BCLK/BIST_RESULT0/AC_SYNC/PG_EINT11_92") (pintype "passive"))
      (node (ref "R20") (pin "2") (pinfunction "2_2") (pintype "passive"))
    )
    (net (code "21") (name "LAN_LED_Y") (class "Default")
      (node (ref "MOD1") (pin "91") (pinfunction "PG13/H_I2S2_DOUT0/H_I2S2_DIN1/BIST_RESULT2/AC_ADCR/PG_EINT13_91") (pintype "passive"))
      (node (ref "R21") (pin "2") (pinfunction "2_2") (pintype "passive"))
    )
    (net (code "22") (name "LINEOUT_L") (class "Default")
      (node (ref "J1") (pin "3") (pinfunction "3_3") (pintype "passive"))
      (node (ref "MOD1") (pin "66") (pinfunction "LINEOUTL_66") (pintype "passive"))
    )
    (net (code "23") (name "LINEOUT_R") (class "Default")
      (node (ref "J1") (pin "4") (pinfunction "4_4") (pintype "passive"))
      (node (ref "MOD1") (pin "67") (pinfunction "LINEOUTR_67") (pintype "passive"))
    )
    (net (code "24") (name "LRADC") (class "Default")
      (node (ref "J1") (pin "2") (pinfunction "2_2") (pintype "passive"))
      (node (ref "MOD1") (pin "64") (pinfunction "LRADC_64") (pintype "passive"))
    )
    (net (code "25") (name "Net-(C12-Pad2)") (class "Default")
      (node (ref "C12") (pin "2") (pinfunction "2_2") (pintype "passive"))
      (node (ref "R13") (pin "1") (pinfunction "1_1") (pintype "passive"))
      (node (ref "R14") (pin "1") (pinfunction "1_1") (pintype "passive"))
    )
    (net (code "26") (name "Net-(C13-Pad2)") (class "Default")
      (node (ref "C13") (pin "2") (pinfunction "2_2") (pintype "passive"))
      (node (ref "R15") (pin "1") (pinfunction "1_1") (pintype "passive"))
      (node (ref "R16") (pin "1") (pinfunction "1_1") (pintype "passive"))
    )
    (net (code "27") (name "Net-(C14-Pad2)") (class "Default")
      (node (ref "C14") (pin "2") (pinfunction "2_2") (pintype "passive"))
      (node (ref "CON5") (pin "4") (pinfunction "TD2-_4") (pintype "bidirectional"))
    )
    (net (code "28") (name "Net-(C16-Pad2)") (class "Default")
      (node (ref "C16") (pin "2") (pinfunction "2_2") (pintype "passive"))
      (node (ref "CON5") (pin "5") (pinfunction "TD2-_5") (pintype "bidirectional"))
    )
    (net (code "29") (name "Net-(CON3-PadCC1)") (class "Default")
      (node (ref "CON3") (pin "CC1") (pinfunction "CC1_CC1") (pintype "bidirectional"))
      (node (ref "R2") (pin "2") (pinfunction "2_2") (pintype "passive"))
    )
    (net (code "30") (name "Net-(CON3-PadCC2)") (class "Default")
      (node (ref "CON3") (pin "CC2") (pinfunction "CC2_CC2") (pintype "bidirectional"))
      (node (ref "R1") (pin "2") (pinfunction "2_2") (pintype "passive"))
    )
    (net (code "31") (name "Net-(CON5-K_GREEN)") (class "Default")
      (node (ref "CON5") (pin "16") (pinfunction "K_GREEN_16") (pintype "bidirectional"))
      (node (ref "R20") (pin "1") (pinfunction "1_1") (pintype "passive"))
    )
    (net (code "32") (name "Net-(CON5-K_YELLOW)") (class "Default")
      (node (ref "CON5") (pin "18") (pinfunction "K_YELLOW_18") (pintype "bidirectional"))
      (node (ref "R21") (pin "1") (pinfunction "1_1") (pintype "passive"))
    )
    (net (code "33") (name "Net-(D3-C)") (class "Default")
      (node (ref "D3") (pin "1") (pinfunction "C_1") (pintype "passive"))
      (node (ref "R7") (pin "2") (pinfunction "2_2") (pintype "passive"))
    )
    (net (code "34") (name "Net-(J4-2)") (class "Default")
      (node (ref "J4") (pin "P$2") (pinfunction "2_P$2") (pintype "bidirectional"))
      (node (ref "J4") (pin "P$4") (pinfunction "4_P$4") (pintype "bidirectional"))
      (node (ref "J5") (pin "1") (pinfunction "1_1") (pintype "passive"))
    )
    (net (code "35") (name "Net-(LED1-PadA)") (class "Default")
      (node (ref "LED1") (pin "A") (pinfunction "A_A") (pintype "passive"))
      (node (ref "R3") (pin "1") (pinfunction "1_1") (pintype "passive"))
    )
    (net (code "36") (name "PH0{slash}UART0-TX") (class "Default")
      (node (ref "J2") (pin "2") (pinfunction "2_2") (pintype "passive"))
      (node (ref "J4") (pin "P$8") (pinfunction "8_P$8") (pintype "bidirectional"))
      (node (ref "MOD1") (pin "36") (pinfunction "PH0/UART0_TX/CAN_TX/PWM3/TWI1_SCK/PH_EINT0_36") (pintype "passive"))
    )
    (net (code "37") (name "PH1{slash}UART0-RX") (class "Default")
      (node (ref "J2") (pin "3") (pinfunction "3_3") (pintype "passive"))
      (node (ref "J4") (pin "P$10") (pinfunction "10_P$10") (pintype "bidirectional"))
      (node (ref "MOD1") (pin "37") (pinfunction "PH1/UART0_RX/CAN_RX/PWM4/TWI1_SDA/PH_EINT1_37") (pintype "passive"))
    )
    (net (code "38") (name "PH2{slash}UART5-TX") (class "Default")
      (node (ref "J4") (pin "P$11") (pinfunction "11_P$11") (pintype "bidirectional"))
      (node (ref "MOD1") (pin "38") (pinfunction "PH2/UART5_TX/SPDIF_CLK/PWM2/TWI2_SCK/PH_EINT2/EPHY-SPD-LED_38") (pintype "passive"))
    )
    (net (code "39") (name "PH3{slash}UART5-RX") (class "Default")
      (node (ref "J4") (pin "P$13") (pinfunction "13_P$13") (pintype "bidirectional"))
      (node (ref "MOD1") (pin "39") (pinfunction "PH3/UART5_RX/SPDIF_IN/PWM1/TWI2_SDA/PH_EINT3/EPHY-LINK-LED_39") (pintype "passive"))
    )
    (net (code "40") (name "PH4") (class "Default")
      (node (ref "J4") (pin "P$18") (pinfunction "18_P$18") (pintype "bidirectional"))
      (node (ref "MOD1") (pin "40") (pinfunction "PH4/SPDIF_OUT/TWI3_SCK/PH_EINT4_40") (pintype "passive"))
    )
    (net (code "41") (name "PH10") (class "Default")
      (node (ref "J4") (pin "P$36") (pinfunction "36_P$36") (pintype "bidirectional"))
      (node (ref "MOD1") (pin "46") (pinfunction "PH10/IR_RX/TCON_TRIG1/PH_EINT10_46") (pintype "passive"))
    )
    (net (code "42") (name "PI0{slash}I2S0-MCLK") (class "Default")
      (node (ref "J4") (pin "P$7") (pinfunction "7_P$7") (pintype "bidirectional"))
      (node (ref "MOD1") (pin "18") (pinfunction "PI0/RGMII_RXD3/RMII_NULL/DMIC_CLK/H_I2S0_MCLK/HDMI_SCL/PI_EINT0_18") (pintype "passive"))
    )
    (net (code "43") (name "PI1{slash}I2S0-BCLK") (class "Default")
      (node (ref "J4") (pin "P$12") (pinfunction "12_P$12") (pintype "bidirectional"))
      (node (ref "MOD1") (pin "19") (pinfunction "PI1/RGMII_RXD2/RMII_NULL/DMIC_DATA0/H_I2S0_BCLK/HDMI_SDA/PI_EINT1_19") (pintype "passive"))
    )
    (net (code "44") (name "PI2{slash}I2S0-LRCK") (class "Default")
      (node (ref "J4") (pin "P$35") (pinfunction "35_P$35") (pintype "bidirectional"))
      (node (ref "MOD1") (pin "20") (pinfunction "PI2/RGMII_RXD1/RMII_RXD1/DMIC_DATA1/H_I2S0_LRCK/HDMI_CEC/PI_EINT2_20") (pintype "passive"))
    )
    (net (code "45") (name "PI3{slash}I2S0-DIN") (class "Default")
      (node (ref "J4") (pin "P$40") (pinfunction "40_P$40") (pintype "bidirectional"))
      (node (ref "MOD1") (pin "21") (pinfunction "PI3/RGMII_RXD0/RMII_RXD0/DMIC_DATA2/H_I2S0_DOUT0/H_I2S0_DIN1/PI_EINT3_21") (pintype "passive"))
    )
    (net (code "46") (name "PI4{slash}I2S0-DOUT") (class "Default")
      (node (ref "J4") (pin "P$38") (pinfunction "38_P$38") (pintype "bidirectional"))
      (node (ref "MOD1") (pin "22") (pinfunction "PI4/RGMII_RXCK/RMII_NULL/DMIC_DATA3/H_I2S0_DIN0/H_I2S0_DOUT1/PI_EINT4_22") (pintype "passive"))
    )
    (net (code "47") (name "PI5{slash}UART2-TX") (class "Default")
      (node (ref "J4") (pin "P$32") (pinfunction "32_P$32") (pintype "bidirectional"))
      (node (ref "MOD1") (pin "23") (pinfunction "PI5/RGMII_RXCTL/RMII_CRS_DV/UART2_TX/TS0_CLK/TWI0_SCK/PI_EINT5_23") (pintype "passive"))
    )
    (net (code "48") (name "PI6{slash}UART2-RX") (class "Default")
      (node (ref "J4") (pin "P$22") (pinfunction "22_P$22") (pintype "bidirectional"))
      (node (ref "MOD1") (pin "24") (pinfunction "PI6/RGMII_NULL/RMII_RXER/UART2_RX/TS0_ERR/TWI0_SDA/PI_EINT6_24") (pintype "passive"))
    )
    (net (code "49") (name "PI7{slash}TWI1-SCK") (class "Default")
      (node (ref "J4") (pin "P$5") (pinfunction "5_P$5") (pintype "bidirectional"))
      (node (ref "MOD1") (pin "25") (pinfunction "PI7/RGMII_TXD3/RMII_NULL/UART2_RTS/TS0_SYNC/TWI1_SCK/PI_EINT7_25") (pintype "passive"))
      (node (ref "R5") (pin "2") (pinfunction "2_2") (pintype "passive"))
    )
    (net (code "50") (name "PI8{slash}TWI1-SDA") (class "Default")
      (node (ref "J4") (pin "P$3") (pinfunction "3_P$3") (pintype "bidirectional"))
      (node (ref "MOD1") (pin "26") (pinfunction "PI8/RGMII_TXD2/RMII_NULL/UART2_CTS/TS0_DVLD/TWI1_SDA/PI_EINT8_26") (pintype "passive"))
      (node (ref "R4") (pin "2") (pinfunction "2_2") (pintype "passive"))
    )
    (net (code "51") (name "PI9{slash}TWI2-SCK") (class "Default")
      (node (ref "J4") (pin "P$28") (pinfunction "28_P$28") (pintype "bidirectional"))
      (node (ref "MOD1") (pin "27") (pinfunction "PI9/RGMII_TXD1/RMII_TXD1/UART3_TX/TS0_D0/TWI2_SCK/PI_EINT9_27") (pintype "passive"))
    )
    (net (code "52") (name "PI10{slash}TWI2-SDA") (class "Default")
      (node (ref "J4") (pin "P$27") (pinfunction "27_P$27") (pintype "bidirectional"))
      (node (ref "MOD1") (pin "28") (pinfunction "PI10/RGMII_TXD0/RMII_TXD0/UART3_RX/TS0_D1/TWI2_SDA/PI_EINT10_28") (pintype "passive"))
    )
    (net (code "53") (name "PI11") (class "Default")
      (node (ref "J4") (pin "P$29") (pinfunction "29_P$29") (pintype "bidirectional"))
      (node (ref "MOD1") (pin "29") (pinfunction "PI11/RGMII_TXCK/RMII_TXCK/UART3_RTS/TS0_D2/PWM1/PI_EINT11_29") (pintype "passive"))
    )
    (net (code "54") (name "PI12") (class "Default")
      (node (ref "J4") (pin "P$31") (pinfunction "31_P$31") (pintype "bidirectional"))
      (node (ref "MOD1") (pin "30") (pinfunction "PI12/RGMII_TXCTL/RMII_TXEN/UART3_CTS/TS0_D3/PWM2/PI_EINT12_30") (pintype "passive"))
    )
    (net (code "55") (name "PI13{slash}UART4-TX{slash}PWM3") (class "Default")
      (node (ref "J4") (pin "P$15") (pinfunction "15_P$15") (pintype "bidirectional"))
      (node (ref "MOD1") (pin "32") (pinfunction "PI13/RGMII_CLKIN/RMII_NULL/UART4_TX/TS0_D4/PWM3/PI_EINT13_32") (pintype "passive"))
    )
    (net (code "56") (name "PI14{slash}UART4-RX{slash}PWM4") (class "Default")
      (node (ref "J4") (pin "P$16") (pinfunction "16_P$16") (pintype "bidirectional"))
      (node (ref "MOD1") (pin "33") (pinfunction "PI14/MDC/UART4_RX/TS0_D5/PWM4/PI_EINT14_33") (pintype "passive"))
    )
    (net (code "57") (name "PI15") (class "Default")
      (node (ref "J4") (pin "P$33") (pinfunction "33_P$33") (pintype "bidirectional"))
      (node (ref "MOD1") (pin "34") (pinfunction "PI15/MDIO/UART4_RTS/TS0_D6/CLK_FANOUT0/PI_EINT15_34") (pintype "passive"))
    )
    (net (code "58") (name "PI16") (class "Default")
      (node (ref "J4") (pin "P$37") (pinfunction "37_P$37") (pintype "bidirectional"))
      (node (ref "MOD1") (pin "35") (pinfunction "PI16/EPHY_25M/UART4_CTS/TS0_D7/CLK_FANOUT1/PI_EINT16_35") (pintype "passive"))
    )
    (net (code "59") (name "RESET") (class "Default")
      (node (ref "MOD1") (pin "53") (pinfunction "RESET_53") (pintype "passive"))
      (node (ref "SW1") (pin "P$1") (pinfunction "1_P$1") (pintype "bidirectional"))
      (node (ref "SW1") (pin "P$2") (pinfunction "1_P$2") (pintype "bidirectional"))
    )
    (net (code "60") (name "RXI_N") (class "Default")
      (node (ref "CON5") (pin "6") (pinfunction "TD2-_6") (pintype "bidirectional"))
      (node (ref "MOD1") (pin "85") (pinfunction "EPHY_RXN_85") (pintype "passive"))
      (node (ref "R16") (pin "2") (pinfunction "2_2") (pintype "passive"))
    )
    (net (code "61") (name "RXI_P") (class "Default")
      (node (ref "CON5") (pin "3") (pinfunction "TD2+_3") (pintype "bidirectional"))
      (node (ref "MOD1") (pin "86") (pinfunction "EPHY_RXP_86") (pintype "passive"))
      (node (ref "R15") (pin "2") (pinfunction "2_2") (pintype "passive"))
    )
    (net (code "62") (name "SCD0-CLK") (class "Default")
      (node (ref "MOD1") (pin "12") (pinfunction "PF2/SDC0_CLK/UART0_TX/PF_EINT2_12") (pintype "passive"))
      (node (ref "R18") (pin "2") (pinfunction "2_2") (pintype "passive"))
    )
    (net (code "63") (name "SCD0-CLK'") (class "Default")
      (node (ref "CON6") (pin "5") (pinfunction "CLK/SCLK_5") (pintype "bidirectional"))
      (node (ref "R18") (pin "1") (pinfunction "1_1") (pintype "passive"))
    )
    (net (code "64") (name "SCD0-CMD") (class "Default")
      (node (ref "CON6") (pin "3") (pinfunction "CMD/DI_3") (pintype "bidirectional"))
      (node (ref "MOD1") (pin "14") (pinfunction "PF3/SDC0_CMD/JTAG_DO/PF_EINT3_14") (pintype "passive"))
      (node (ref "R17") (pin "1") (pinfunction "1_1") (pintype "passive"))
    )
    (net (code "65") (name "SCD0-D0") (class "Default")
      (node (ref "CON6") (pin "7") (pinfunction "DAT0/D0_7") (pintype "bidirectional"))
      (node (ref "MOD1") (pin "11") (pinfunction "PF1/SDC0_D0/JTAG_DI/PF_EINT1_11") (pintype "passive"))
    )
    (net (code "66") (name "SCD0-D1") (class "Default")
      (node (ref "CON6") (pin "8") (pinfunction "DAT1_8") (pintype "bidirectional"))
      (node (ref "MOD1") (pin "10") (pinfunction "PF0/SDC0_D1/JTAG_MS/PF_EINT0_10") (pintype "passive"))
    )
    (net (code "67") (name "SCD0-D2") (class "Default")
      (node (ref "CON6") (pin "1") (pinfunction "DAT2_1") (pintype "bidirectional"))
      (node (ref "MOD1") (pin "16") (pinfunction "PF5/SDC0_D2/JTAG_CK/PF_EINT5_16") (pintype "passive"))
    )
    (net (code "68") (name "SCD0-D3") (class "Default")
      (node (ref "CON6") (pin "2") (pinfunction "DAT3/CS_2") (pintype "bidirectional"))
      (node (ref "MOD1") (pin "15") (pinfunction "PF4/SDC0_D3/UART0_RX/PF_EINT4_15") (pintype "passive"))
    )
    (net (code "69") (name "SCD0-DET") (class "Default")
      (node (ref "CON6") (pin "9") (pinfunction "CD_SW_9") (pintype "bidirectional"))
      (node (ref "MOD1") (pin "17") (pinfunction "PF6/PF_EINT6_17") (pintype "passive"))
      (node (ref "R19") (pin "1") (pinfunction "1_1") (pintype "passive"))
      (node (ref "TP4") (pin "TP") (pinfunction "TP_TP") (pintype "bidirectional"))
    )
    (net (code "70") (name "SPI1-CLK") (class "Default")
      (node (ref "J4") (pin "P$23") (pinfunction "23_P$23") (pintype "bidirectional"))
      (node (ref "MOD1") (pin "42") (pinfunction "PH6/UART2_RX/H_I2S3_BCLK/SPI1_CLK/TWI4_SCK/PH_EINT6_42") (pintype "passive"))
    )
    (net (code "71") (name "SPI1-CS0") (class "Default")
      (node (ref "J4") (pin "P$24") (pinfunction "24_P$24") (pintype "bidirectional"))
      (node (ref "MOD1") (pin "41") (pinfunction "PH5/UART2_TX/H_I2S3_MCLK/SPI1_CS0/TWI3_SDA/PH_EINT5_41") (pintype "passive"))
    )
    (net (code "72") (name "SPI1-CS1") (class "Default")
      (node (ref "J4") (pin "P$26") (pinfunction "26_P$26") (pintype "bidirectional"))
      (node (ref "MOD1") (pin "45") (pinfunction "PH9/H_I2S3_DIN0/SPI1_CS1/H_I2S3_DOUT1/PH_EINT9_45") (pintype "passive"))
    )
    (net (code "73") (name "SPI1-MISO") (class "Default")
      (node (ref "J4") (pin "P$21") (pinfunction "21_P$21") (pintype "bidirectional"))
      (node (ref "MOD1") (pin "44") (pinfunction "PH8/UART2_CTS/H_I2S3_DOUT0/SPI1_MISO/H_I2S3_DIN1/PH_EINT8_44") (pintype "passive"))
    )
    (net (code "74") (name "SPI1-MOSI") (class "Default")
      (node (ref "J4") (pin "P$19") (pinfunction "19_P$19") (pintype "bidirectional"))
      (node (ref "MOD1") (pin "43") (pinfunction "PH7/UART2_RTS/H_I2S3_LRCK/SPI1_MOSI/TWI4_SDA/PH_EINT7_43") (pintype "passive"))
    )
    (net (code "75") (name "TR0_TAP") (class "Default")
      (node (ref "CON5") (pin "11") (pinfunction "VC1_11") (pintype "bidirectional"))
      (node (ref "J6") (pin "2") (pinfunction "2_2") (pintype "bidirectional"))
    )
    (net (code "76") (name "TR1_TAP") (class "Default")
      (node (ref "CON5") (pin "12") (pinfunction "VC2_12") (pintype "bidirectional"))
      (node (ref "J6") (pin "1") (pinfunction "1_1") (pintype "bidirectional"))
    )
    (net (code "77") (name "TR2_TAP") (class "Default")
      (node (ref "CON5") (pin "13") (pinfunction "VC3_13") (pintype "bidirectional"))
      (node (ref "J6") (pin "4") (pinfunction "4_4") (pintype "bidirectional"))
    )
    (net (code "78") (name "TR3_TAP") (class "Default")
      (node (ref "CON5") (pin "14") (pinfunction "VC4_14") (pintype "bidirectional"))
      (node (ref "J6") (pin "3") (pinfunction "3_3") (pintype "bidirectional"))
    )
    (net (code "79") (name "TXO_N") (class "Default")
      (node (ref "CON5") (pin "2") (pinfunction "TD1-_2") (pintype "bidirectional"))
      (node (ref "MOD1") (pin "87") (pinfunction "EPHY_TXN_87") (pintype "passive"))
      (node (ref "R14") (pin "2") (pinfunction "2_2") (pintype "passive"))
    )
    (net (code "80") (name "TXO_P") (class "Default")
      (node (ref "CON5") (pin "1") (pinfunction "TD1+_1") (pintype "bidirectional"))
      (node (ref "MOD1") (pin "88") (pinfunction "EPHY_TXP_88") (pintype "passive"))
      (node (ref "R13") (pin "2") (pinfunction "2_2") (pintype "passive"))
    )
    (net (code "81") (name "USB0_N") (class "Default")
      (node (ref "CON3") (pin "DN1") (pinfunction "DN1_DN1") (pintype "bidirectional"))
      (node (ref "CON3") (pin "DN2") (pinfunction "DN2_DN2") (pintype "bidirectional"))
      (node (ref "D1") (pin "3") (pinfunction "I/O_2_3") (pintype "bidirectional"))
      (node (ref "MOD1") (pin "61") (pinfunction "USB0_DM_61") (pintype "passive"))
    )
    (net (code "82") (name "USB0_P") (class "Default")
      (node (ref "CON3") (pin "DP1") (pinfunction "DP1_DP1") (pintype "bidirectional"))
      (node (ref "CON3") (pin "DP2") (pinfunction "DP2_DP2") (pintype "bidirectional"))
      (node (ref "D1") (pin "1") (pinfunction "I/O_1_1") (pintype "bidirectional"))
      (node (ref "MOD1") (pin "62") (pinfunction "USB0_DP_62") (pintype "passive"))
    )
    (net (code "83") (name "USB1_N") (class "Default")
      (node (ref "CON1") (pin "DM") (pinfunction "D-_DM") (pintype "bidirectional"))
      (node (ref "D2") (pin "4") (pinfunction "I/O_3_4") (pintype "bidirectional"))
      (node (ref "MOD1") (pin "55") (pinfunction "USB1_DM_55") (pintype "passive"))
    )
    (net (code "84") (name "USB1_P") (class "Default")
      (node (ref "CON1") (pin "DP") (pinfunction "D+_DP") (pintype "bidirectional"))
      (node (ref "D2") (pin "6") (pinfunction "I/O_4_6") (pintype "bidirectional"))
      (node (ref "MOD1") (pin "56") (pinfunction "USB1_DP_56") (pintype "passive"))
    )
    (net (code "85") (name "USB2_N") (class "Default")
      (node (ref "CON2") (pin "DM") (pinfunction "D-_DM") (pintype "bidirectional"))
      (node (ref "D2") (pin "1") (pinfunction "I/O_1_1") (pintype "bidirectional"))
      (node (ref "MOD1") (pin "58") (pinfunction "USB2_DM_58") (pintype "passive"))
    )
    (net (code "86") (name "USB2_P") (class "Default")
      (node (ref "CON2") (pin "DP") (pinfunction "D+_DP") (pintype "bidirectional"))
      (node (ref "D2") (pin "3") (pinfunction "I/O_2_3") (pintype "bidirectional"))
      (node (ref "MOD1") (pin "59") (pinfunction "USB2_DP_59") (pintype "passive"))
    )
    (net (code "87") (name "VCC") (class "Default")
      (node (ref "C10") (pin "2") (pinfunction "2_2") (pintype "passive"))
      (node (ref "C15") (pin "2") (pinfunction "2_2") (pintype "passive"))
      (node (ref "C8") (pin "2") (pinfunction "2_2") (pintype "passive"))
      (node (ref "C9") (pin "2") (pinfunction "2_2") (pintype "passive"))
      (node (ref "CON5") (pin "15") (pinfunction "A_GREEN_15") (pintype "bidirectional"))
      (node (ref "CON5") (pin "17") (pinfunction "A_YELLOW_17") (pintype "bidirectional"))
      (node (ref "CON6") (pin "4") (pinfunction "VCC_4") (pintype "bidirectional"))
      (node (ref "D3") (pin "2") (pinfunction "A_2") (pintype "passive"))
      (node (ref "IC1") (pin "2") (pinfunction "VOUT_2") (pintype "output"))
      (node (ref "IC1") (pin "4") (pinfunction "TAB_4") (pintype "output"))
      (node (ref "J4") (pin "P$1") (pinfunction "1_P$1") (pintype "bidirectional"))
      (node (ref "J4") (pin "P$17") (pinfunction "17_P$17") (pintype "bidirectional"))
      (node (ref "R17") (pin "2") (pinfunction "2_2") (pintype "passive"))
      (node (ref "R19") (pin "2") (pinfunction "2_2") (pintype "passive"))
      (node (ref "R3") (pin "2") (pinfunction "2_2") (pintype "passive"))
      (node (ref "R4") (pin "1") (pinfunction "1_1") (pintype "passive"))
      (node (ref "R5") (pin "1") (pinfunction "1_1") (pintype "passive"))
      (node (ref "TP3") (pin "TP") (pinfunction "TP_TP") (pintype "bidirectional"))
    )
    (net (code "88") (name "VUSB_IN") (class "Default")
      (node (ref "C5") (pin "2") (pinfunction "2_2") (pintype "passive"))
      (node (ref "CON3") (pin "VBUS@1") (pinfunction "VBUS_VBUS@1") (pintype "bidirectional"))
      (node (ref "CON3") (pin "VBUS@2") (pinfunction "VBUS_VBUS@2") (pintype "bidirectional"))
      (node (ref "D1") (pin "5") (pinfunction "REF_5") (pintype "bidirectional"))
      (node (ref "J3") (pin "2") (pinfunction "2_2") (pintype "passive"))
      (node (ref "L1") (pin "1") (pinfunction "1_1") (pintype "passive"))
    )
    (net (code "89") (name "unconnected-(CON3-PadSBU1)") (class "Default")
      (node (ref "CON3") (pin "SBU1") (pinfunction "SBU1_SBU1") (pintype "bidirectional"))
    )
    (net (code "90") (name "unconnected-(CON3-PadSBU2)") (class "Default")
      (node (ref "CON3") (pin "SBU2") (pinfunction "SBU2_SBU2") (pintype "bidirectional"))
    )
    (net (code "91") (name "unconnected-(CON4-UTILITY{slash}HEAC+-Pad17)") (class "Default")
      (node (ref "CON4") (pin "17") (pinfunction "UTILITY/HEAC+_17") (pintype "passive"))
    )
    (net (code "92") (name "unconnected-(CON5-TD3+-Pad7)") (class "Default")
      (node (ref "CON5") (pin "7") (pinfunction "TD3+_7") (pintype "bidirectional"))
    )
    (net (code "93") (name "unconnected-(CON5-TD3--Pad8)") (class "Default")
      (node (ref "CON5") (pin "8") (pinfunction "TD3-_8") (pintype "bidirectional"))
    )
    (net (code "94") (name "unconnected-(CON5-TD4+-Pad9)") (class "Default")
      (node (ref "CON5") (pin "9") (pinfunction "TD4+_9") (pintype "bidirectional"))
    )
    (net (code "95") (name "unconnected-(CON5-TD4--Pad10)") (class "Default")
      (node (ref "CON5") (pin "10") (pinfunction "TD4-_10") (pintype "bidirectional"))
    )
    (net (code "96") (name "unconnected-(D1-I{slash}O_3-Pad4)") (class "Default")
      (node (ref "D1") (pin "4") (pinfunction "I/O_3_4") (pintype "bidirectional"))
    )
    (net (code "97") (name "unconnected-(D1-I{slash}O_4-Pad6)") (class "Default")
      (node (ref "D1") (pin "6") (pinfunction "I/O_4_6") (pintype "bidirectional"))
    )
    (net (code "98") (name "unconnected-(MOD1-AP-CLK24M-O-Pad90)") (class "Default")
      (node (ref "MOD1") (pin "90") (pinfunction "AP-CLK24M-O_90") (pintype "passive"))
    )
    (net (code "99") (name "unconnected-(MOD1-PC0{slash}SPI0_CLK{slash}PC_EINT0-Pad6)") (class "Default")
      (node (ref "MOD1") (pin "6") (pinfunction "PC0/SPI0_CLK/PC_EINT0_6") (pintype "passive"))
    )
    (net (code "100") (name "unconnected-(MOD1-PC2{slash}SPI0_MOSI{slash}PC_EINT2-Pad7)") (class "Default")
      (node (ref "MOD1") (pin "7") (pinfunction "PC2/SPI0_MOSI/PC_EINT2_7") (pintype "passive"))
    )
    (net (code "101") (name "unconnected-(MOD1-PC3{slash}SPI0_CS0{slash}BOOT_SEL1{slash}PC_EINT3-Pad9)") (class "Default")
      (node (ref "MOD1") (pin "9") (pinfunction "PC3/SPI0_CS0/BOOT_SEL1/PC_EINT3_9") (pintype "passive"))
    )
    (net (code "102") (name "unconnected-(MOD1-PC4{slash}SPI0_MISO{slash}BOOT_SEL2{slash}PC_EINT4-Pad8)") (class "Default")
      (node (ref "MOD1") (pin "8") (pinfunction "PC4/SPI0_MISO/BOOT_SEL2/PC_EINT4_8") (pintype "passive"))
    )
    (net (code "103") (name "unconnected-(MOD1-PG0{slash}SDC1_CLK{slash}PG_EINT0-Pad100)") (class "Default")
      (node (ref "MOD1") (pin "100") (pinfunction "PG0/SDC1_CLK/PG_EINT0_100") (pintype "passive"))
    )
    (net (code "104") (name "unconnected-(MOD1-PG1{slash}SDC1_CMD{slash}PG_EINT1-Pad101)") (class "Default")
      (node (ref "MOD1") (pin "101") (pinfunction "PG1/SDC1_CMD/PG_EINT1_101") (pintype "passive"))
    )
    (net (code "105") (name "unconnected-(MOD1-PG2{slash}SDC1_D0{slash}PG_EINT2-Pad102)") (class "Default")
      (node (ref "MOD1") (pin "102") (pinfunction "PG2/SDC1_D0/PG_EINT2_102") (pintype "passive"))
    )
    (net (code "106") (name "unconnected-(MOD1-PG3{slash}SDC1_D1{slash}PG_EINT3-Pad103)") (class "Default")
      (node (ref "MOD1") (pin "103") (pinfunction "PG3/SDC1_D1/PG_EINT3_103") (pintype "passive"))
    )
    (net (code "107") (name "unconnected-(MOD1-PG4{slash}SDC1_D2{slash}PG_EINT4-Pad104)") (class "Default")
      (node (ref "MOD1") (pin "104") (pinfunction "PG4/SDC1_D2/PG_EINT4_104") (pintype "passive"))
    )
    (net (code "108") (name "unconnected-(MOD1-PG5{slash}SDC1_D3{slash}PG_EINT5-Pad105)") (class "Default")
      (node (ref "MOD1") (pin "105") (pinfunction "PG5/SDC1_D3/PG_EINT5_105") (pintype "passive"))
    )
    (net (code "109") (name "unconnected-(MOD1-PG6{slash}UART1_TX{slash}JTAG_MS{slash}PG_EINT6-Pad1)") (class "Default")
      (node (ref "MOD1") (pin "1") (pinfunction "PG6/UART1_TX/JTAG_MS/PG_EINT6_1") (pintype "passive"))
    )
    (net (code "110") (name "unconnected-(MOD1-PG7{slash}UART1_RX{slash}JTAG_CK{slash}PG_EINT7-Pad2)") (class "Default")
      (node (ref "MOD1") (pin "2") (pinfunction "PG7/UART1_RX/JTAG_CK/PG_EINT7_2") (pintype "passive"))
    )
    (net (code "111") (name "unconnected-(MOD1-PG8{slash}UART1_RTS{slash}PLL_LOCK_DBG{slash}JTAG_DO{slash}PG_EINT8-Pad3)") (class "Default")
      (node (ref "MOD1") (pin "3") (pinfunction "PG8/UART1_RTS/PLL_LOCK_DBG/JTAG_DO/PG_EINT8_3") (pintype "passive"))
    )
    (net (code "112") (name "unconnected-(MOD1-PG9{slash}UART1_CTS{slash}JTAG_DI{slash}AC_ADCY{slash}PG_EINT9-Pad4)") (class "Default")
      (node (ref "MOD1") (pin "4") (pinfunction "PG9/UART1_CTS/JTAG_DI/AC_ADCY/PG_EINT9_4") (pintype "passive"))
    )
    (net (code "113") (name "unconnected-(MOD1-PG10{slash}H_I2S2_MCLK{slash}X32KFOUT{slash}AC_MCLK{slash}PG_EINT10-Pad5)") (class "Default")
      (node (ref "MOD1") (pin "5") (pinfunction "PG10/H_I2S2_MCLK/X32KFOUT/AC_MCLK/PG_EINT10_5") (pintype "passive"))
    )
    (net (code "114") (name "unconnected-(MOD1-PG12{slash}H_I2S2_LRCK{slash}BIST_RESULT1{slash}AC_ADCL{slash}PG_EINT12-Pad94)") (class "Default")
      (node (ref "MOD1") (pin "94") (pinfunction "PG12/H_I2S2_LRCK/BIST_RESULT1/AC_ADCL/PG_EINT12_94") (pintype "passive"))
    )
    (net (code "115") (name "unconnected-(MOD1-PG14{slash}H_I2S2_DIN0{slash}H_I2S2_DOUT1{slash}BIST_RESULT3{slash}AC_ADCX{slash}PG_EINT14-Pad93)") (class "Default")
      (node (ref "MOD1") (pin "93") (pinfunction "PG14/H_I2S2_DIN0/H_I2S2_DOUT1/BIST_RESULT3/AC_ADCX/PG_EINT14_93") (pintype "passive"))
    )
    (net (code "116") (name "unconnected-(MOD1-PG15{slash}UART2_TX{slash}TWI4_SCK{slash}PG_EINT15-Pad95)") (class "Default")
      (node (ref "MOD1") (pin "95") (pinfunction "PG15/UART2_TX/TWI4_SCK/PG_EINT15_95") (pintype "passive"))
    )
    (net (code "117") (name "unconnected-(MOD1-PG16{slash}UART2_RX{slash}TWI4_SDA{slash}PG_EINT16-Pad96)") (class "Default")
      (node (ref "MOD1") (pin "96") (pinfunction "PG16/UART2_RX/TWI4_SDA/PG_EINT16_96") (pintype "passive"))
    )
    (net (code "118") (name "unconnected-(MOD1-PG17{slash}UART2_RTS{slash}MCSI_SCK{slash}TWI3_SCK{slash}PG_EINT17-Pad97)") (class "Default")
      (node (ref "MOD1") (pin "97") (pinfunction "PG17/UART2_RTS/MCSI_SCK/TWI3_SCK/PG_EINT17_97") (pintype "passive"))
    )
    (net (code "119") (name "unconnected-(MOD1-PG18{slash}UART2_CTS{slash}MCSI_SDA{slash}TWI3_SDA{slash}PG_EINT18-Pad99)") (class "Default")
      (node (ref "MOD1") (pin "99") (pinfunction "PG18/UART2_CTS/MCSI_SDA/TWI3_SDA/PG_EINT18_99") (pintype "passive"))
    )
    (net (code "120") (name "unconnected-(MOD1-PG19{slash}MCSI_MCLK{slash}PWM1{slash}PG_EINT19-Pad98)") (class "Default")
      (node (ref "MOD1") (pin "98") (pinfunction "PG19/MCSI_MCLK/PWM1/PG_EINT19_98") (pintype "passive"))
    )
    (net (code "121") (name "unconnected-(MOD1-PWRON-Pad47)") (class "Default")
      (node (ref "MOD1") (pin "47") (pinfunction "PWRON_47") (pintype "passive"))
    )
    (net (code "122") (name "unconnected-(MOD1-TV_OUT-Pad65)") (class "Default")
      (node (ref "MOD1") (pin "65") (pinfunction "TV_OUT_65") (pintype "passive"))
    )
    (net (code "123") (name "unconnected-(MOD1-VCC3V3-Pad48)") (class "Default")
      (node (ref "MOD1") (pin "48") (pinfunction "VCC3V3_48") (pintype "output"))
    )
  )
)
